# Schematic.net
KiCad netlist of a schematic drawn in EAGLE
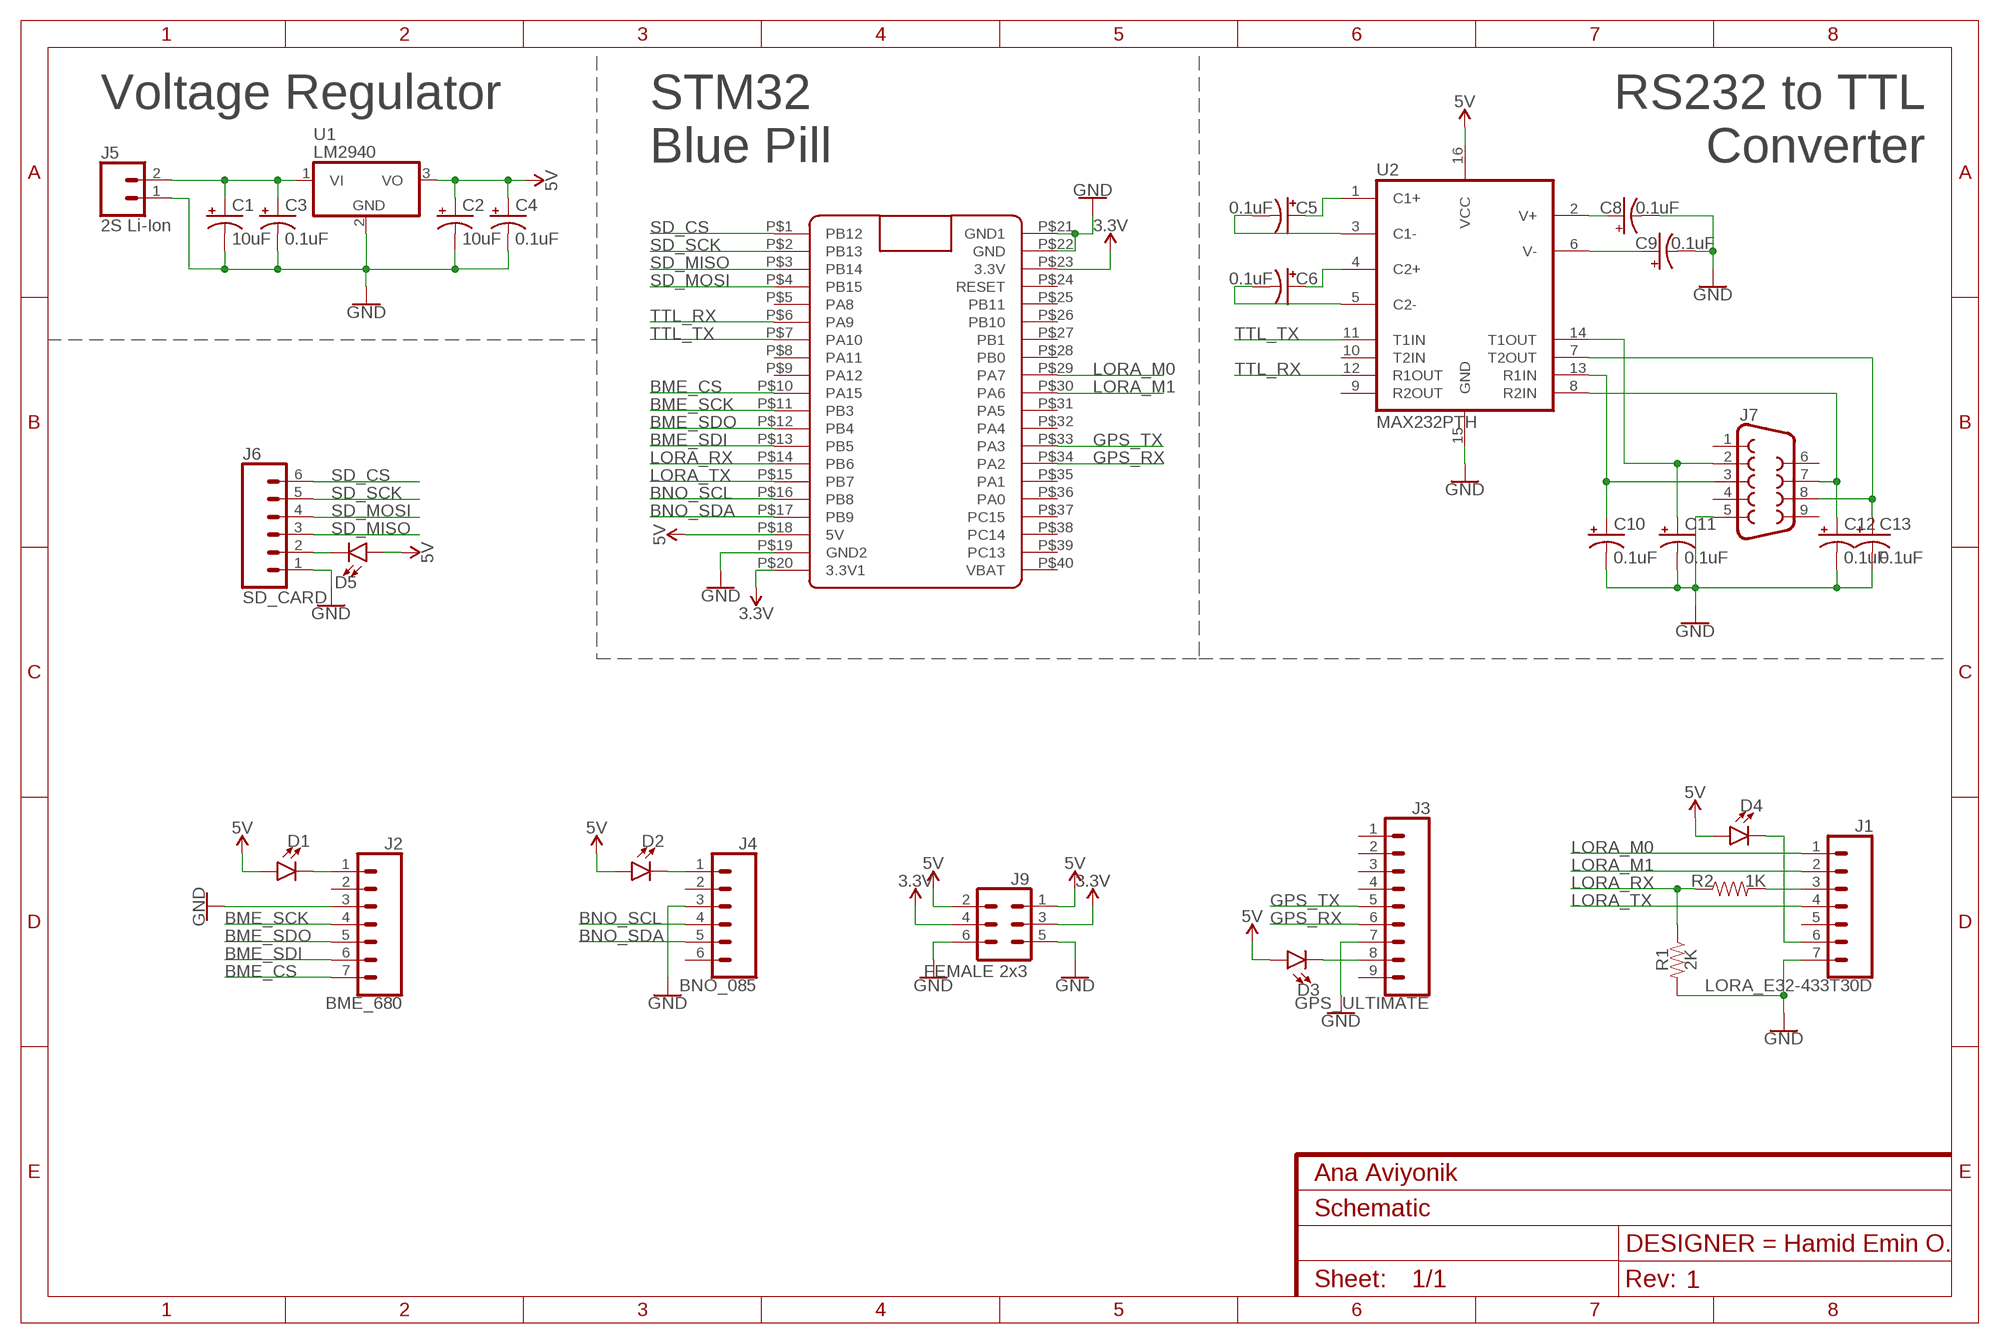
[diagram p0: schematic, sheet 1]

(export (version "E")
  (design (tool "Eeschema 10.0.6"))
  (components
    (comp (ref "C1")
      (value "10uF")
      (footprint "eagle-import:CPOL-RADIAL-2.5MM-5MM-KIT")
      (libsource (lib "eagle-import") (part "10UF-POLAR-RADIAL-2.5MM-KIT-25V-20%"))
    )
    (comp (ref "C2")
      (value "10uF")
      (footprint "eagle-import:CPOL-RADIAL-2.5MM-5MM-KIT")
      (libsource (lib "eagle-import") (part "10UF-POLAR-RADIAL-2.5MM-KIT-25V-20%"))
    )
    (comp (ref "C3")
      (value "0.1uF")
      (footprint "eagle-import:CPOL-RADIAL-2.5MM-5MM-KIT")
      (libsource (lib "eagle-import") (part "10UF-POLAR-RADIAL-2.5MM-KIT-25V-20%"))
    )
    (comp (ref "C4")
      (value "0.1uF")
      (footprint "eagle-import:CPOL-RADIAL-2.5MM-5MM-KIT")
      (libsource (lib "eagle-import") (part "10UF-POLAR-RADIAL-2.5MM-KIT-25V-20%"))
    )
    (comp (ref "C5")
      (value "0.1uF")
      (footprint "eagle-import:CPOL-RADIAL-2.5MM-5MM-KIT")
      (libsource (lib "eagle-import") (part "10UF-POLAR-RADIAL-2.5MM-KIT-25V-20%"))
    )
    (comp (ref "C6")
      (value "0.1uF")
      (footprint "eagle-import:CPOL-RADIAL-2.5MM-5MM-KIT")
      (libsource (lib "eagle-import") (part "10UF-POLAR-RADIAL-2.5MM-KIT-25V-20%"))
    )
    (comp (ref "C8")
      (value "0.1uF")
      (footprint "eagle-import:CPOL-RADIAL-2.5MM-5MM-KIT")
      (libsource (lib "eagle-import") (part "10UF-POLAR-RADIAL-2.5MM-KIT-25V-20%"))
    )
    (comp (ref "C9")
      (value "0.1uF")
      (footprint "eagle-import:CPOL-RADIAL-2.5MM-5MM-KIT")
      (libsource (lib "eagle-import") (part "10UF-POLAR-RADIAL-2.5MM-KIT-25V-20%"))
    )
    (comp (ref "C10")
      (value "0.1uF")
      (footprint "eagle-import:CPOL-RADIAL-2.5MM-5MM-KIT")
      (libsource (lib "eagle-import") (part "10UF-POLAR-RADIAL-2.5MM-KIT-25V-20%"))
    )
    (comp (ref "C11")
      (value "0.1uF")
      (footprint "eagle-import:CPOL-RADIAL-2.5MM-5MM-KIT")
      (libsource (lib "eagle-import") (part "10UF-POLAR-RADIAL-2.5MM-KIT-25V-20%"))
    )
    (comp (ref "C12")
      (value "0.1uF")
      (footprint "eagle-import:CPOL-RADIAL-2.5MM-5MM-KIT")
      (libsource (lib "eagle-import") (part "10UF-POLAR-RADIAL-2.5MM-KIT-25V-20%"))
    )
    (comp (ref "C13")
      (value "0.1uF")
      (footprint "eagle-import:CPOL-RADIAL-2.5MM-5MM-KIT")
      (libsource (lib "eagle-import") (part "10UF-POLAR-RADIAL-2.5MM-KIT-25V-20%"))
    )
    (comp (ref "D1")
      (value "LED-3MM-NO_SILK")
      (footprint "eagle-import:LED_3MM-NS")
      (libsource (lib "eagle-import") (part "LED-3MM-NO_SILK"))
    )
    (comp (ref "D2")
      (value "LED-3MM-NO_SILK")
      (footprint "eagle-import:LED_3MM-NS")
      (libsource (lib "eagle-import") (part "LED-3MM-NO_SILK"))
    )
    (comp (ref "D3")
      (value "LED-3MM-NO_SILK")
      (footprint "eagle-import:LED_3MM-NS")
      (libsource (lib "eagle-import") (part "LED-3MM-NO_SILK"))
    )
    (comp (ref "D4")
      (value "LED-3MM-NO_SILK")
      (footprint "eagle-import:LED_3MM-NS")
      (libsource (lib "eagle-import") (part "LED-3MM-NO_SILK"))
    )
    (comp (ref "D5")
      (value "LED-3MM-NO_SILK")
      (footprint "eagle-import:LED_3MM-NS")
      (libsource (lib "eagle-import") (part "LED-3MM-NO_SILK"))
    )
    (comp (ref "J1")
      (value "LORA_E32-433T30D")
      (footprint "eagle-import:1X07")
      (libsource (lib "eagle-import") (part "CONN_07"))
    )
    (comp (ref "J2")
      (value "BME_680")
      (footprint "eagle-import:1X07")
      (libsource (lib "eagle-import") (part "CONN_07"))
    )
    (comp (ref "J3")
      (value "GPS_ULTIMATE")
      (footprint "eagle-import:1X09")
      (libsource (lib "eagle-import") (part "CONN_09"))
    )
    (comp (ref "J4")
      (value "BNO_085")
      (footprint "eagle-import:1X06")
      (libsource (lib "eagle-import") (part "CONN_06SILK_FEMALE_PTH"))
    )
    (comp (ref "J5")
      (value "2S Li-Ion")
      (footprint "eagle-import:1X02")
      (libsource (lib "eagle-import") (part "CONN_02"))
    )
    (comp (ref "J6")
      (value "SD_CARD")
      (footprint "eagle-import:1X06")
      (libsource (lib "eagle-import") (part "CONN_06SILK_FEMALE_PTH"))
    )
    (comp (ref "J7")
      (value "DB9FEMALE")
      (footprint "eagle-import:DB9")
      (libsource (lib "eagle-import") (part "DB9FEMALE"))
    )
    (comp (ref "J9")
      (value "FEMALE 2x3")
      (footprint "eagle-import:2X3")
      (libsource (lib "eagle-import") (part "CONN_03X2FEMALE"))
    )
    (comp (ref "R1")
      (value "2K")
      (footprint "eagle-import:AXIAL-0.1-KIT")
      (libsource (lib "eagle-import") (part "1KOHM-VERT_KIT-1/4W-5%"))
    )
    (comp (ref "R2")
      (value "1K")
      (footprint "eagle-import:AXIAL-0.1-KIT")
      (libsource (lib "eagle-import") (part "1KOHM-VERT_KIT-1/4W-5%"))
    )
    (comp (ref "STM32BLUEPILL")
      (value "STM32 Blue Pill")
      (footprint "eagle-import:BLUE_PILL")
      (libsource (lib "eagle-import") (part "BLUE_PILL"))
    )
    (comp (ref "U1")
      (value "LM2940")
      (footprint "eagle-import:TO220V")
      (libsource (lib "eagle-import") (part "78TV6"))
    )
    (comp (ref "U2")
      (value "MAX232PTH")
      (footprint "eagle-import:DIL16")
      (libsource (lib "eagle-import") (part "MAX232PTH"))
    )
  )
  (nets
    (net (code "1") (name "/BME_CS") (class "Default")
      (node (ref "J2") (pin "7") (pinfunction "7_7") (pintype "passive"))
      (node (ref "STM32BLUEPILL") (pin "P$10") (pinfunction "PA15_P$10") (pintype "bidirectional"))
    )
    (net (code "2") (name "/BME_SCK") (class "Default")
      (node (ref "J2") (pin "4") (pinfunction "4_4") (pintype "passive"))
      (node (ref "STM32BLUEPILL") (pin "P$11") (pinfunction "PB3_P$11") (pintype "bidirectional"))
    )
    (net (code "3") (name "/BME_SDI") (class "Default")
      (node (ref "J2") (pin "6") (pinfunction "6_6") (pintype "passive"))
      (node (ref "STM32BLUEPILL") (pin "P$13") (pinfunction "PB5_P$13") (pintype "bidirectional"))
    )
    (net (code "4") (name "/BME_SDO") (class "Default")
      (node (ref "J2") (pin "5") (pinfunction "5_5") (pintype "passive"))
      (node (ref "STM32BLUEPILL") (pin "P$12") (pinfunction "PB4_P$12") (pintype "bidirectional"))
    )
    (net (code "5") (name "/BNO_SCL") (class "Default")
      (node (ref "J4") (pin "4") (pinfunction "4_4") (pintype "passive"))
      (node (ref "STM32BLUEPILL") (pin "P$16") (pinfunction "PB8_P$16") (pintype "bidirectional"))
    )
    (net (code "6") (name "/BNO_SDA") (class "Default")
      (node (ref "J4") (pin "5") (pinfunction "5_5") (pintype "passive"))
      (node (ref "STM32BLUEPILL") (pin "P$17") (pinfunction "PB9_P$17") (pintype "bidirectional"))
    )
    (net (code "7") (name "/GPS_RX") (class "Default")
      (node (ref "J3") (pin "6") (pinfunction "6_6") (pintype "passive"))
      (node (ref "STM32BLUEPILL") (pin "P$34") (pinfunction "PA2_P$34") (pintype "bidirectional"))
    )
    (net (code "8") (name "/GPS_TX") (class "Default")
      (node (ref "J3") (pin "5") (pinfunction "5_5") (pintype "passive"))
      (node (ref "STM32BLUEPILL") (pin "P$33") (pinfunction "PA3_P$33") (pintype "bidirectional"))
    )
    (net (code "9") (name "/LORA_M0") (class "Default")
      (node (ref "J1") (pin "1") (pinfunction "1_1") (pintype "passive"))
      (node (ref "STM32BLUEPILL") (pin "P$29") (pinfunction "PA7_P$29") (pintype "bidirectional"))
    )
    (net (code "10") (name "/LORA_M1") (class "Default")
      (node (ref "J1") (pin "2") (pinfunction "2_2") (pintype "passive"))
      (node (ref "STM32BLUEPILL") (pin "P$30") (pinfunction "PA6_P$30") (pintype "bidirectional"))
    )
    (net (code "11") (name "/LORA_RX") (class "Default")
      (node (ref "R1") (pin "P$1") (pinfunction "1_P$1") (pintype "passive"))
      (node (ref "R2") (pin "P$1") (pinfunction "1_P$1") (pintype "passive"))
      (node (ref "STM32BLUEPILL") (pin "P$14") (pinfunction "PB6_P$14") (pintype "bidirectional"))
    )
    (net (code "12") (name "/LORA_TX") (class "Default")
      (node (ref "J1") (pin "4") (pinfunction "4_4") (pintype "passive"))
      (node (ref "STM32BLUEPILL") (pin "P$15") (pinfunction "PB7_P$15") (pintype "bidirectional"))
    )
    (net (code "13") (name "/SD_CS") (class "Default")
      (node (ref "J6") (pin "6") (pinfunction "6_6") (pintype "passive"))
      (node (ref "STM32BLUEPILL") (pin "P$1") (pinfunction "PB12_P$1") (pintype "bidirectional"))
    )
    (net (code "14") (name "/SD_MISO") (class "Default")
      (node (ref "J6") (pin "3") (pinfunction "3_3") (pintype "passive"))
      (node (ref "STM32BLUEPILL") (pin "P$3") (pinfunction "PB14_P$3") (pintype "bidirectional"))
    )
    (net (code "15") (name "/SD_MOSI") (class "Default")
      (node (ref "J6") (pin "4") (pinfunction "4_4") (pintype "passive"))
      (node (ref "STM32BLUEPILL") (pin "P$4") (pinfunction "PB15_P$4") (pintype "bidirectional"))
    )
    (net (code "16") (name "/SD_SCK") (class "Default")
      (node (ref "J6") (pin "5") (pinfunction "5_5") (pintype "passive"))
      (node (ref "STM32BLUEPILL") (pin "P$2") (pinfunction "PB13_P$2") (pintype "bidirectional"))
    )
    (net (code "17") (name "/TTL_RX") (class "Default")
      (node (ref "STM32BLUEPILL") (pin "P$6") (pinfunction "PA9_P$6") (pintype "bidirectional"))
      (node (ref "U2") (pin "12") (pinfunction "R1OUT_12") (pintype "output"))
    )
    (net (code "18") (name "/TTL_TX") (class "Default")
      (node (ref "STM32BLUEPILL") (pin "P$7") (pinfunction "PA10_P$7") (pintype "bidirectional"))
      (node (ref "U2") (pin "11") (pinfunction "T1IN_11") (pintype "input"))
    )
    (net (code "19") (name "3.3V") (class "Default")
      (node (ref "J9") (pin "3") (pinfunction "3_3") (pintype "bidirectional"))
      (node (ref "J9") (pin "4") (pinfunction "4_4") (pintype "bidirectional"))
      (node (ref "STM32BLUEPILL") (pin "P$20") (pinfunction "3.3V1_P$20") (pintype "bidirectional"))
      (node (ref "STM32BLUEPILL") (pin "P$23") (pinfunction "3.3V_P$23") (pintype "bidirectional"))
    )
    (net (code "20") (name "5V") (class "Default")
      (node (ref "C2") (pin "1") (pinfunction "+_1") (pintype "passive"))
      (node (ref "C4") (pin "1") (pinfunction "+_1") (pintype "passive"))
      (node (ref "D1") (pin "A") (pinfunction "A_A") (pintype "passive"))
      (node (ref "D2") (pin "A") (pinfunction "A_A") (pintype "passive"))
      (node (ref "D3") (pin "A") (pinfunction "A_A") (pintype "passive"))
      (node (ref "D4") (pin "A") (pinfunction "A_A") (pintype "passive"))
      (node (ref "D5") (pin "A") (pinfunction "A_A") (pintype "passive"))
      (node (ref "J9") (pin "1") (pinfunction "1_1") (pintype "bidirectional"))
      (node (ref "J9") (pin "2") (pinfunction "2_2") (pintype "bidirectional"))
      (node (ref "STM32BLUEPILL") (pin "P$18") (pinfunction "5V_P$18") (pintype "bidirectional"))
      (node (ref "U1") (pin "3") (pinfunction "VO_3") (pintype "passive"))
      (node (ref "U2") (pin "16") (pinfunction "VCC_16") (pintype "bidirectional"))
    )
    (net (code "21") (name "GND") (class "Default")
      (node (ref "C1") (pin "2") (pinfunction "-_2") (pintype "passive"))
      (node (ref "C10") (pin "2") (pinfunction "-_2") (pintype "passive"))
      (node (ref "C11") (pin "2") (pinfunction "-_2") (pintype "passive"))
      (node (ref "C12") (pin "2") (pinfunction "-_2") (pintype "passive"))
      (node (ref "C13") (pin "2") (pinfunction "-_2") (pintype "passive"))
      (node (ref "C2") (pin "2") (pinfunction "-_2") (pintype "passive"))
      (node (ref "C3") (pin "2") (pinfunction "-_2") (pintype "passive"))
      (node (ref "C4") (pin "2") (pinfunction "-_2") (pintype "passive"))
      (node (ref "C8") (pin "2") (pinfunction "-_2") (pintype "passive"))
      (node (ref "C9") (pin "2") (pinfunction "-_2") (pintype "passive"))
      (node (ref "J1") (pin "7") (pinfunction "7_7") (pintype "passive"))
      (node (ref "J2") (pin "3") (pinfunction "3_3") (pintype "passive"))
      (node (ref "J3") (pin "7") (pinfunction "7_7") (pintype "passive"))
      (node (ref "J4") (pin "3") (pinfunction "3_3") (pintype "passive"))
      (node (ref "J5") (pin "1") (pinfunction "1_1") (pintype "passive"))
      (node (ref "J6") (pin "1") (pinfunction "1_1") (pintype "passive"))
      (node (ref "J7") (pin "5") (pinfunction "5_5") (pintype "passive"))
      (node (ref "J9") (pin "5") (pinfunction "5_5") (pintype "bidirectional"))
      (node (ref "J9") (pin "6") (pinfunction "6_6") (pintype "bidirectional"))
      (node (ref "R1") (pin "P$2") (pinfunction "2_P$2") (pintype "passive"))
      (node (ref "STM32BLUEPILL") (pin "P$19") (pinfunction "GND2_P$19") (pintype "bidirectional"))
      (node (ref "STM32BLUEPILL") (pin "P$21") (pinfunction "GND1_P$21") (pintype "power_in"))
      (node (ref "STM32BLUEPILL") (pin "P$22") (pinfunction "GND_P$22") (pintype "bidirectional"))
      (node (ref "U1") (pin "2") (pinfunction "GND_2") (pintype "passive"))
      (node (ref "U2") (pin "15") (pinfunction "GND_15") (pintype "bidirectional"))
    )
    (net (code "22") (name "Net-(C1-+)") (class "Default")
      (node (ref "C1") (pin "1") (pinfunction "+_1") (pintype "passive"))
      (node (ref "C3") (pin "1") (pinfunction "+_1") (pintype "passive"))
      (node (ref "J5") (pin "2") (pinfunction "2_2") (pintype "passive"))
      (node (ref "U1") (pin "1") (pinfunction "VI_1") (pintype "input"))
    )
    (net (code "23") (name "Net-(C5-+)") (class "Default")
      (node (ref "C5") (pin "1") (pinfunction "+_1") (pintype "passive"))
      (node (ref "U2") (pin "1") (pinfunction "C1+_1") (pintype "bidirectional"))
    )
    (net (code "24") (name "Net-(C5--)") (class "Default")
      (node (ref "C5") (pin "2") (pinfunction "-_2") (pintype "passive"))
      (node (ref "U2") (pin "3") (pinfunction "C1-_3") (pintype "bidirectional"))
    )
    (net (code "25") (name "Net-(C6-+)") (class "Default")
      (node (ref "C6") (pin "1") (pinfunction "+_1") (pintype "passive"))
      (node (ref "U2") (pin "4") (pinfunction "C2+_4") (pintype "bidirectional"))
    )
    (net (code "26") (name "Net-(C6--)") (class "Default")
      (node (ref "C6") (pin "2") (pinfunction "-_2") (pintype "passive"))
      (node (ref "U2") (pin "5") (pinfunction "C2-_5") (pintype "bidirectional"))
    )
    (net (code "27") (name "Net-(C8-+)") (class "Default")
      (node (ref "C8") (pin "1") (pinfunction "+_1") (pintype "passive"))
      (node (ref "U2") (pin "2") (pinfunction "V+_2") (pintype "bidirectional"))
    )
    (net (code "28") (name "Net-(C9-+)") (class "Default")
      (node (ref "C9") (pin "1") (pinfunction "+_1") (pintype "passive"))
      (node (ref "U2") (pin "6") (pinfunction "V-_6") (pintype "bidirectional"))
    )
    (net (code "29") (name "Net-(C10-+)") (class "Default")
      (node (ref "C10") (pin "1") (pinfunction "+_1") (pintype "passive"))
      (node (ref "J7") (pin "3") (pinfunction "3_3") (pintype "passive"))
      (node (ref "U2") (pin "13") (pinfunction "R1IN_13") (pintype "input"))
    )
    (net (code "30") (name "Net-(C11-+)") (class "Default")
      (node (ref "C11") (pin "1") (pinfunction "+_1") (pintype "passive"))
      (node (ref "J7") (pin "2") (pinfunction "2_2") (pintype "passive"))
      (node (ref "U2") (pin "14") (pinfunction "T1OUT_14") (pintype "output"))
    )
    (net (code "31") (name "Net-(C12-+)") (class "Default")
      (node (ref "C12") (pin "1") (pinfunction "+_1") (pintype "passive"))
      (node (ref "J7") (pin "7") (pinfunction "7_7") (pintype "passive"))
      (node (ref "U2") (pin "8") (pinfunction "R2IN_8") (pintype "input"))
    )
    (net (code "32") (name "Net-(C13-+)") (class "Default")
      (node (ref "C13") (pin "1") (pinfunction "+_1") (pintype "passive"))
      (node (ref "J7") (pin "8") (pinfunction "8_8") (pintype "passive"))
      (node (ref "U2") (pin "7") (pinfunction "T2OUT_7") (pintype "output"))
    )
    (net (code "33") (name "Net-(D1-C)") (class "Default")
      (node (ref "D1") (pin "K") (pinfunction "C_K") (pintype "passive"))
      (node (ref "J2") (pin "1") (pinfunction "1_1") (pintype "passive"))
    )
    (net (code "34") (name "Net-(D2-C)") (class "Default")
      (node (ref "D2") (pin "K") (pinfunction "C_K") (pintype "passive"))
      (node (ref "J4") (pin "1") (pinfunction "1_1") (pintype "passive"))
    )
    (net (code "35") (name "Net-(D3-C)") (class "Default")
      (node (ref "D3") (pin "K") (pinfunction "C_K") (pintype "passive"))
      (node (ref "J3") (pin "8") (pinfunction "8_8") (pintype "passive"))
    )
    (net (code "36") (name "Net-(D4-C)") (class "Default")
      (node (ref "D4") (pin "K") (pinfunction "C_K") (pintype "passive"))
      (node (ref "J1") (pin "6") (pinfunction "6_6") (pintype "passive"))
    )
    (net (code "37") (name "Net-(D5-C)") (class "Default")
      (node (ref "D5") (pin "K") (pinfunction "C_K") (pintype "passive"))
      (node (ref "J6") (pin "2") (pinfunction "2_2") (pintype "passive"))
    )
    (net (code "38") (name "Net-(R2-2)") (class "Default")
      (node (ref "J1") (pin "3") (pinfunction "3_3") (pintype "passive"))
      (node (ref "R2") (pin "P$2") (pinfunction "2_P$2") (pintype "passive"))
    )
    (net (code "39") (name "unconnected-(J1-Pad5)") (class "Default")
      (node (ref "J1") (pin "5") (pinfunction "5_5") (pintype "passive"))
    )
    (net (code "40") (name "unconnected-(J2-Pad2)") (class "Default")
      (node (ref "J2") (pin "2") (pinfunction "2_2") (pintype "passive"))
    )
    (net (code "41") (name "unconnected-(J3-Pad1)") (class "Default")
      (node (ref "J3") (pin "1") (pinfunction "1_1") (pintype "passive"))
    )
    (net (code "42") (name "unconnected-(J3-Pad2)") (class "Default")
      (node (ref "J3") (pin "2") (pinfunction "2_2") (pintype "passive"))
    )
    (net (code "43") (name "unconnected-(J3-Pad3)") (class "Default")
      (node (ref "J3") (pin "3") (pinfunction "3_3") (pintype "passive"))
    )
    (net (code "44") (name "unconnected-(J3-Pad4)") (class "Default")
      (node (ref "J3") (pin "4") (pinfunction "4_4") (pintype "passive"))
    )
    (net (code "45") (name "unconnected-(J3-Pad9)") (class "Default")
      (node (ref "J3") (pin "9") (pinfunction "9_9") (pintype "passive"))
    )
    (net (code "46") (name "unconnected-(J4-Pad2)") (class "Default")
      (node (ref "J4") (pin "2") (pinfunction "2_2") (pintype "passive"))
    )
    (net (code "47") (name "unconnected-(J4-Pad6)") (class "Default")
      (node (ref "J4") (pin "6") (pinfunction "6_6") (pintype "passive"))
    )
    (net (code "48") (name "unconnected-(J7-Pad1)") (class "Default")
      (node (ref "J7") (pin "1") (pinfunction "1_1") (pintype "passive"))
    )
    (net (code "49") (name "unconnected-(J7-Pad4)") (class "Default")
      (node (ref "J7") (pin "4") (pinfunction "4_4") (pintype "passive"))
    )
    (net (code "50") (name "unconnected-(J7-Pad6)") (class "Default")
      (node (ref "J7") (pin "6") (pinfunction "6_6") (pintype "passive"))
    )
    (net (code "51") (name "unconnected-(J7-Pad9)") (class "Default")
      (node (ref "J7") (pin "9") (pinfunction "9_9") (pintype "passive"))
    )
    (net (code "52") (name "unconnected-(STM32BLUEPILL-PA0-PadP$36)") (class "Default")
      (node (ref "STM32BLUEPILL") (pin "P$36") (pinfunction "PA0_P$36") (pintype "bidirectional"))
    )
    (net (code "53") (name "unconnected-(STM32BLUEPILL-PA1-PadP$35)") (class "Default")
      (node (ref "STM32BLUEPILL") (pin "P$35") (pinfunction "PA1_P$35") (pintype "bidirectional"))
    )
    (net (code "54") (name "unconnected-(STM32BLUEPILL-PA4-PadP$32)") (class "Default")
      (node (ref "STM32BLUEPILL") (pin "P$32") (pinfunction "PA4_P$32") (pintype "bidirectional"))
    )
    (net (code "55") (name "unconnected-(STM32BLUEPILL-PA5-PadP$31)") (class "Default")
      (node (ref "STM32BLUEPILL") (pin "P$31") (pinfunction "PA5_P$31") (pintype "bidirectional"))
    )
    (net (code "56") (name "unconnected-(STM32BLUEPILL-PA8-PadP$5)") (class "Default")
      (node (ref "STM32BLUEPILL") (pin "P$5") (pinfunction "PA8_P$5") (pintype "bidirectional"))
    )
    (net (code "57") (name "unconnected-(STM32BLUEPILL-PA11-PadP$8)") (class "Default")
      (node (ref "STM32BLUEPILL") (pin "P$8") (pinfunction "PA11_P$8") (pintype "bidirectional"))
    )
    (net (code "58") (name "unconnected-(STM32BLUEPILL-PA12-PadP$9)") (class "Default")
      (node (ref "STM32BLUEPILL") (pin "P$9") (pinfunction "PA12_P$9") (pintype "bidirectional"))
    )
    (net (code "59") (name "unconnected-(STM32BLUEPILL-PB0-PadP$28)") (class "Default")
      (node (ref "STM32BLUEPILL") (pin "P$28") (pinfunction "PB0_P$28") (pintype "bidirectional"))
    )
    (net (code "60") (name "unconnected-(STM32BLUEPILL-PB1-PadP$27)") (class "Default")
      (node (ref "STM32BLUEPILL") (pin "P$27") (pinfunction "PB1_P$27") (pintype "bidirectional"))
    )
    (net (code "61") (name "unconnected-(STM32BLUEPILL-PB10-PadP$26)") (class "Default")
      (node (ref "STM32BLUEPILL") (pin "P$26") (pinfunction "PB10_P$26") (pintype "bidirectional"))
    )
    (net (code "62") (name "unconnected-(STM32BLUEPILL-PB11-PadP$25)") (class "Default")
      (node (ref "STM32BLUEPILL") (pin "P$25") (pinfunction "PB11_P$25") (pintype "bidirectional"))
    )
    (net (code "63") (name "unconnected-(STM32BLUEPILL-PC13-PadP$39)") (class "Default")
      (node (ref "STM32BLUEPILL") (pin "P$39") (pinfunction "PC13_P$39") (pintype "bidirectional"))
    )
    (net (code "64") (name "unconnected-(STM32BLUEPILL-PC14-PadP$38)") (class "Default")
      (node (ref "STM32BLUEPILL") (pin "P$38") (pinfunction "PC14_P$38") (pintype "bidirectional"))
    )
    (net (code "65") (name "unconnected-(STM32BLUEPILL-PC15-PadP$37)") (class "Default")
      (node (ref "STM32BLUEPILL") (pin "P$37") (pinfunction "PC15_P$37") (pintype "bidirectional"))
    )
    (net (code "66") (name "unconnected-(STM32BLUEPILL-RESET-PadP$24)") (class "Default")
      (node (ref "STM32BLUEPILL") (pin "P$24") (pinfunction "RESET_P$24") (pintype "bidirectional"))
    )
    (net (code "67") (name "unconnected-(STM32BLUEPILL-VBAT-PadP$40)") (class "Default")
      (node (ref "STM32BLUEPILL") (pin "P$40") (pinfunction "VBAT_P$40") (pintype "bidirectional"))
    )
    (net (code "68") (name "unconnected-(U2-R2OUT-Pad9)") (class "Default")
      (node (ref "U2") (pin "9") (pinfunction "R2OUT_9") (pintype "output"))
    )
    (net (code "69") (name "unconnected-(U2-T2IN-Pad10)") (class "Default")
      (node (ref "U2") (pin "10") (pinfunction "T2IN_10") (pintype "input"))
    )
  )
)
